# Indication.net
KiCad netlist of a schematic drawn in Altium Designer
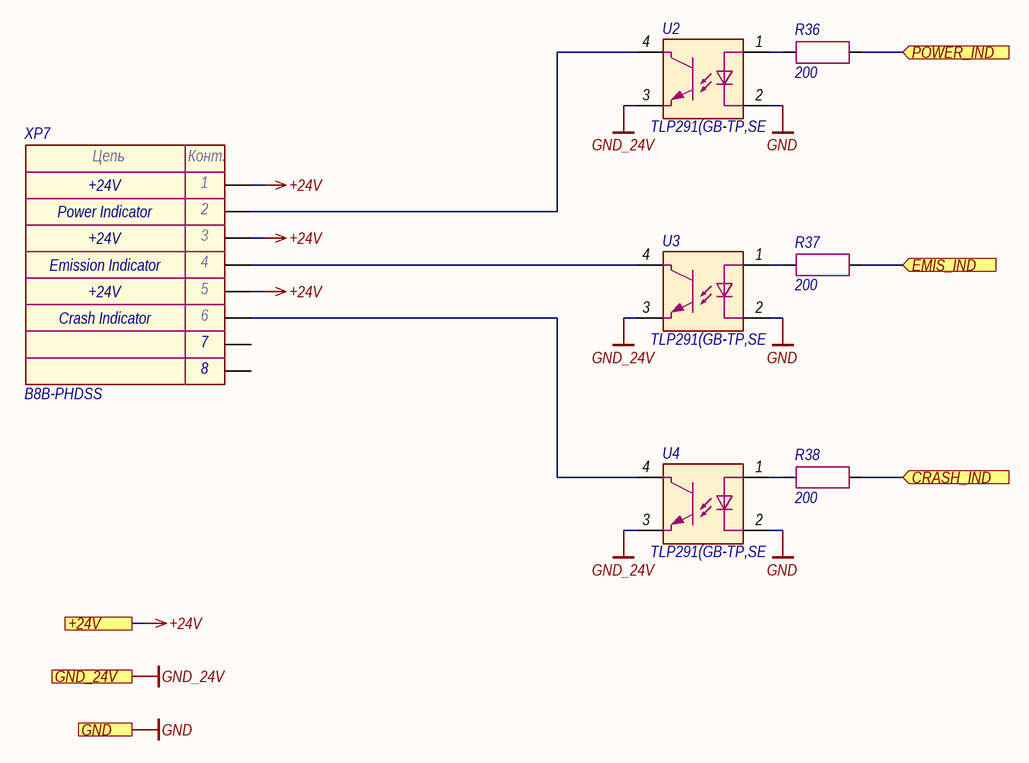
[diagram p0: Indication.SchDoc]

(export (version "E")
  (design (tool "Eeschema 10.0.6"))
  (components
    (comp (ref "R36")
      (value "200")
      (footprint "Pcb_library:RES_0603")
      (fields (field (name "MANUFACTURER") "Yageo"))
      (libsource (lib "Schem_library") (part "Resistor"))
    )
    (comp (ref "R37")
      (value "200")
      (footprint "Pcb_library:RES_0603")
      (fields (field (name "MANUFACTURER") "Yageo"))
      (libsource (lib "Schem_library") (part "Resistor"))
    )
    (comp (ref "R38")
      (value "200")
      (footprint "Pcb_library:RES_0603")
      (fields (field (name "MANUFACTURER") "Yageo"))
      (libsource (lib "Schem_library") (part "Resistor"))
    )
    (comp (ref "U2")
      (value "TLP291(GB-TP,SE")
      (footprint "Pcb_library:11-3C1")
      (fields (field (name "MANUFACTURER") "Toshiba"))
      (libsource (lib "Schem_library") (part "TLP291"))
    )
    (comp (ref "U3")
      (value "TLP291(GB-TP,SE")
      (footprint "Pcb_library:11-3C1")
      (fields (field (name "MANUFACTURER") "Toshiba"))
      (libsource (lib "Schem_library") (part "TLP291"))
    )
    (comp (ref "U4")
      (value "TLP291(GB-TP,SE")
      (footprint "Pcb_library:11-3C1")
      (fields (field (name "MANUFACTURER") "Toshiba"))
      (libsource (lib "Schem_library") (part "TLP291"))
    )
    (comp (ref "XP7")
      (value "B8B-PHDSS")
      (footprint "Pcb_library:B8B-PHDSS")
      (fields (field (name "MANUFACTURER") "JST"))
      (libsource (lib "Schem_library") (part "Connector-8"))
    )
  )
  (nets
    (net (code "1") (name "+24V") (class "Default")
      (node (ref "XP7") (pin "1") (pintype "passive"))
      (node (ref "XP7") (pin "3") (pintype "passive"))
      (node (ref "XP7") (pin "5") (pintype "passive"))
    )
    (net (code "2") (name "/CRASH_IND") (class "Default")
      (node (ref "R38") (pin "2") (pinfunction "2_2") (pintype "passive"))
    )
    (net (code "3") (name "/EMIS_IND") (class "Default")
      (node (ref "R37") (pin "2") (pinfunction "2_2") (pintype "passive"))
    )
    (net (code "4") (name "/POWER_IND") (class "Default")
      (node (ref "R36") (pin "2") (pinfunction "2_2") (pintype "passive"))
    )
    (net (code "5") (name "GND") (class "Default")
      (node (ref "U2") (pin "2") (pintype "passive"))
      (node (ref "U3") (pin "2") (pintype "passive"))
      (node (ref "U4") (pin "2") (pintype "passive"))
    )
    (net (code "6") (name "GND_24V") (class "Default")
      (node (ref "U2") (pin "3") (pintype "passive"))
      (node (ref "U3") (pin "3") (pintype "passive"))
      (node (ref "U4") (pin "3") (pintype "passive"))
    )
    (net (code "7") (name "Net-(R36-Pad1)") (class "Default")
      (node (ref "R36") (pin "1") (pinfunction "1_1") (pintype "passive"))
      (node (ref "U2") (pin "1") (pintype "passive"))
    )
    (net (code "8") (name "Net-(R37-Pad1)") (class "Default")
      (node (ref "R37") (pin "1") (pinfunction "1_1") (pintype "passive"))
      (node (ref "U3") (pin "1") (pintype "passive"))
    )
    (net (code "9") (name "Net-(R38-Pad1)") (class "Default")
      (node (ref "R38") (pin "1") (pinfunction "1_1") (pintype "passive"))
      (node (ref "U4") (pin "1") (pintype "passive"))
    )
    (net (code "10") (name "Net-(U2-Pad4)") (class "Default")
      (node (ref "U2") (pin "4") (pintype "passive"))
      (node (ref "XP7") (pin "2") (pintype "passive"))
    )
    (net (code "11") (name "Net-(U3-Pad4)") (class "Default")
      (node (ref "U3") (pin "4") (pintype "passive"))
      (node (ref "XP7") (pin "4") (pintype "passive"))
    )
    (net (code "12") (name "Net-(U4-Pad4)") (class "Default")
      (node (ref "U4") (pin "4") (pintype "passive"))
      (node (ref "XP7") (pin "6") (pintype "passive"))
    )
    (net (code "13") (name "unconnected-(XP7-Pad7)") (class "Default")
      (node (ref "XP7") (pin "7") (pintype "passive"))
    )
    (net (code "14") (name "unconnected-(XP7-Pad8)") (class "Default")
      (node (ref "XP7") (pin "8") (pintype "passive"))
    )
  )
)
